# Charger.net
KiCad netlist of a schematic drawn in Altium Designer
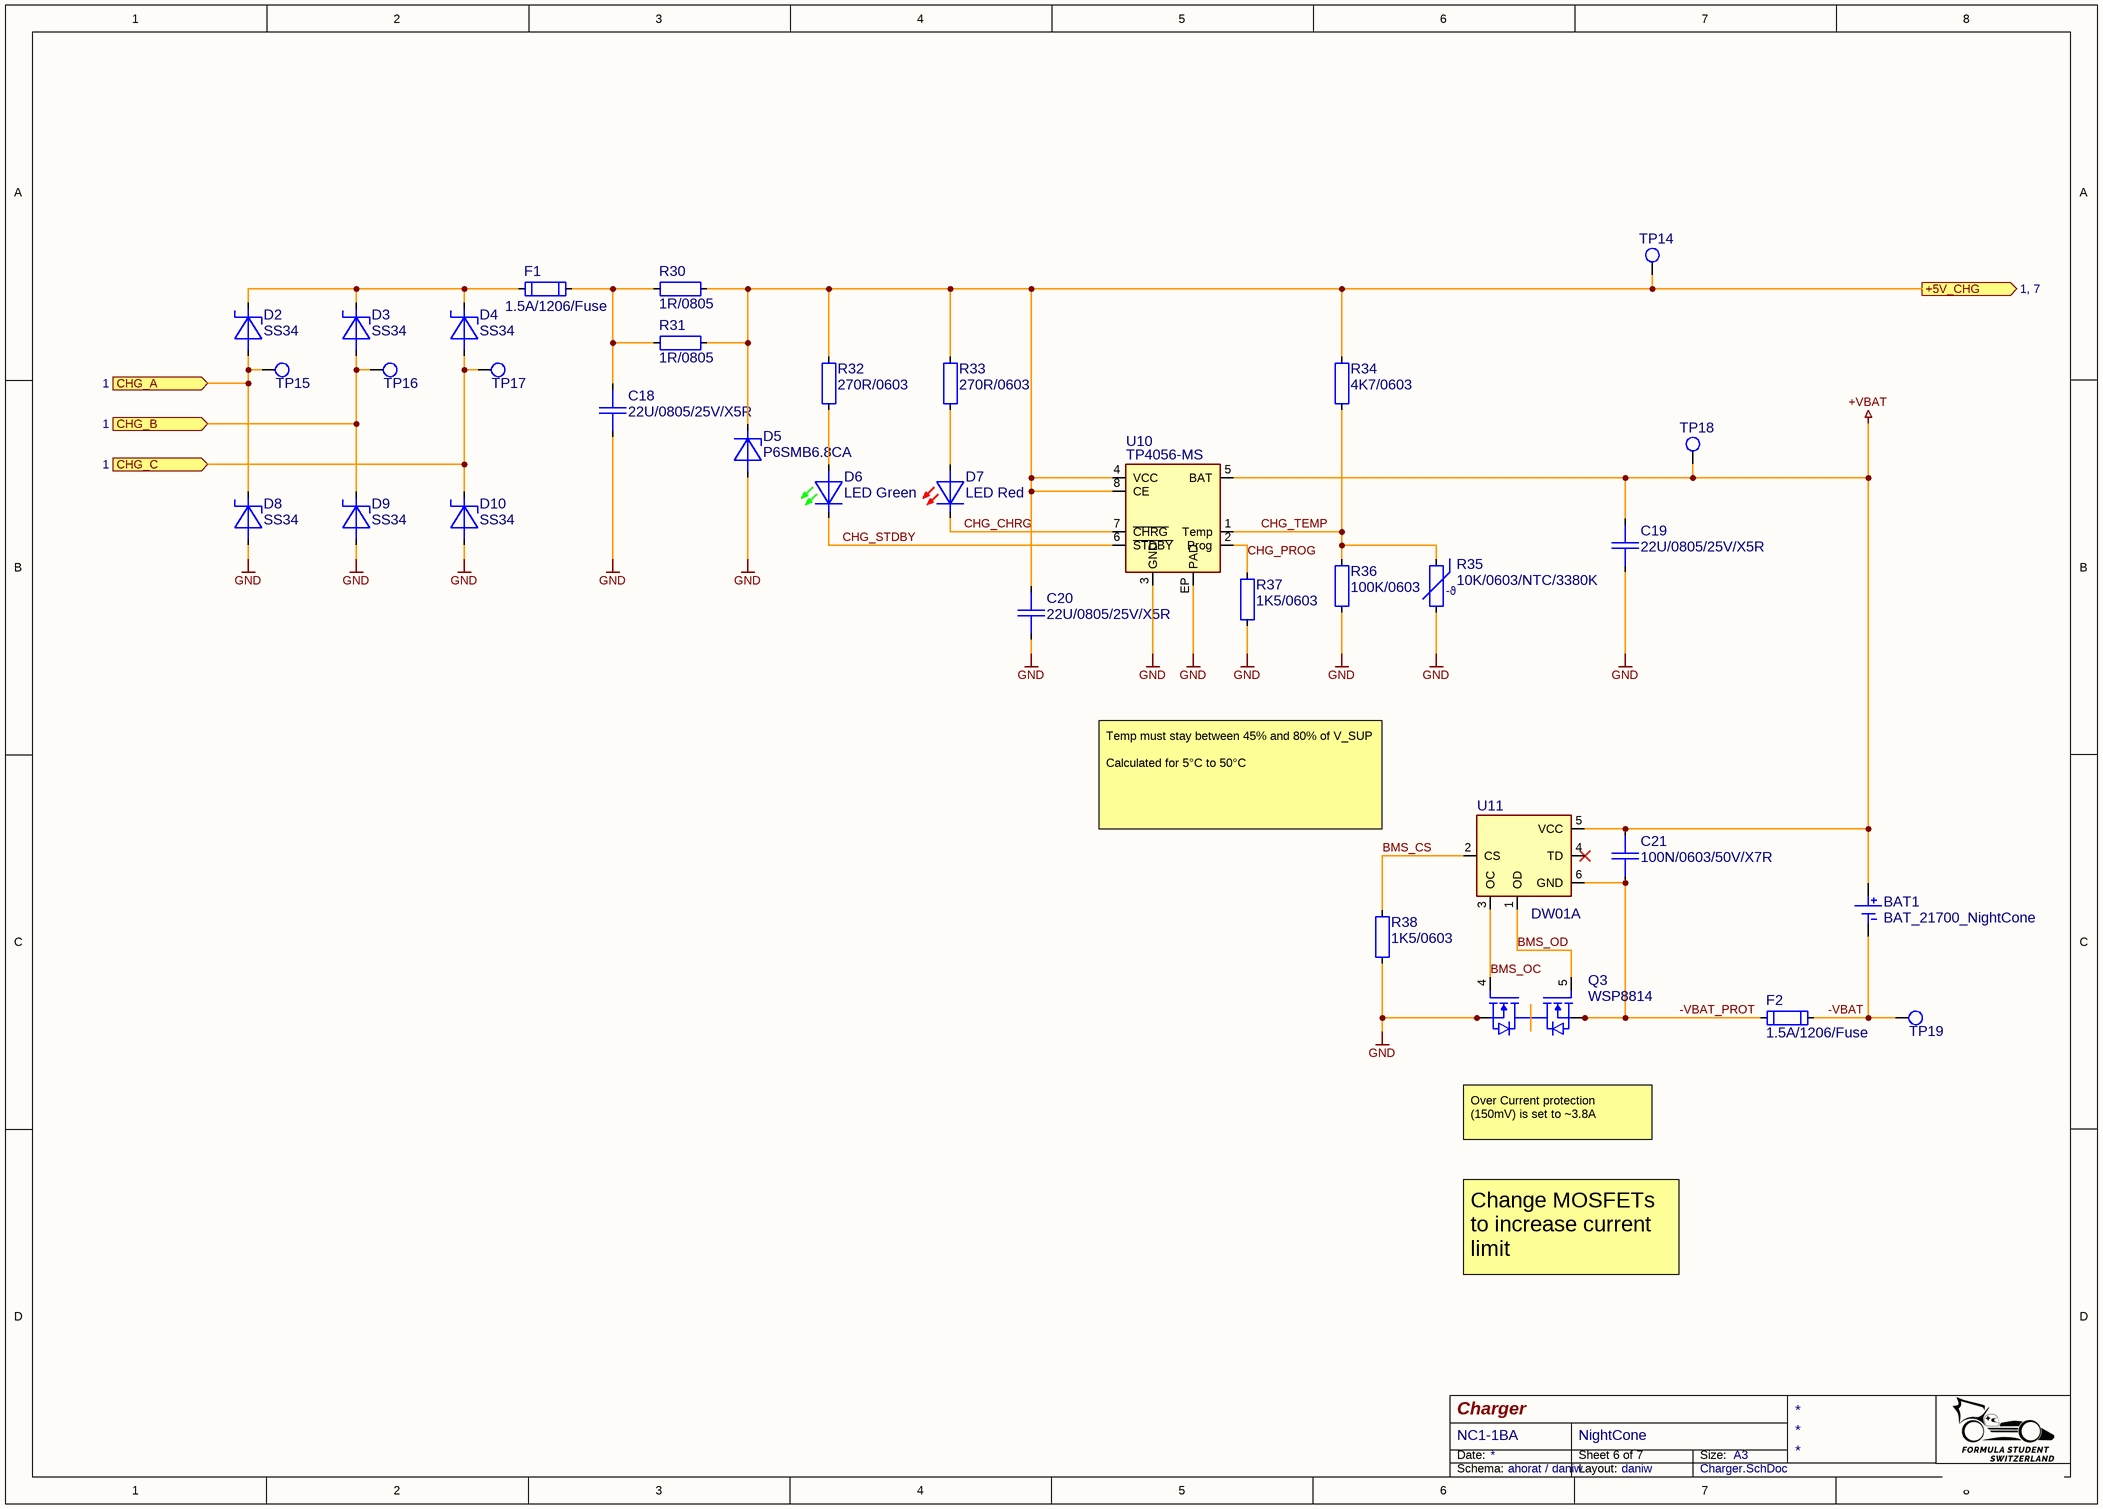
[diagram p0: Charger.SchDoc]

(export (version "E")
  (design (tool "Eeschema 10.0.6"))
  (components
    (comp (ref "BAT1")
      (value "BAT_21700_NightCone")
      (footprint "BAT-21700-NC")
      (description "21700 Battery cell for FSCH nightcone project")
      (fields (field (name "MANUFACTURER") "NONE"))
      (libsource (lib "daniw_altium_lib") (part "Battery_1"))
    )
    (comp (ref "C18")
      (value "22U/0805/25V/X5R")
      (footprint "CAP0805_X7R")
      (description "CAP SM 0805 22uF 25V X5R")
      (fields (field (name "MANUFACTURER") "GENERIC"))
      (libsource (lib "daniw_altium_lib") (part "C"))
    )
    (comp (ref "C19")
      (value "22U/0805/25V/X5R")
      (footprint "CAP0805_X7R")
      (description "CAP SM 0805 22uF 25V X5R")
      (fields (field (name "MANUFACTURER") "GENERIC"))
      (libsource (lib "daniw_altium_lib") (part "C"))
    )
    (comp (ref "C20")
      (value "22U/0805/25V/X5R")
      (footprint "CAP0805_X7R")
      (description "CAP SM 0805 22uF 25V X5R")
      (fields (field (name "MANUFACTURER") "GENERIC"))
      (libsource (lib "daniw_altium_lib") (part "C"))
    )
    (comp (ref "C21")
      (value "100N/0603/50V/X7R")
      (footprint "CAP0603_X7R")
      (description "CAP SM 0603 100nF 50V X7R")
      (fields (field (name "MANUFACTURER") "GENERIC"))
      (libsource (lib "daniw_altium_lib") (part "C"))
    )
    (comp (ref "D2")
      (value "SS34")
      (footprint "DIOM5226X230")
      (description "Si Shottky Diode 3A DO-214AC")
      (fields (field (name "MANUFACTURER") "GENERIC"))
      (libsource (lib "daniw_altium_lib") (part "D_Schottky"))
    )
    (comp (ref "D3")
      (value "SS34")
      (footprint "DIOM5226X230")
      (description "Si Shottky Diode 3A DO-214AC")
      (fields (field (name "MANUFACTURER") "GENERIC"))
      (libsource (lib "daniw_altium_lib") (part "D_Schottky"))
    )
    (comp (ref "D4")
      (value "SS34")
      (footprint "DIOM5226X230")
      (description "Si Shottky Diode 3A DO-214AC")
      (fields (field (name "MANUFACTURER") "GENERIC"))
      (libsource (lib "daniw_altium_lib") (part "D_Schottky"))
    )
    (comp (ref "D5")
      (value "P6SMB6.8CA")
      (footprint "DIOM5436X265")
      (description "10.5V 6.45V 5.8V SMB(DO-214AA) TVS")
      (fields (field (name "MANUFACTURER") "Littelfuse Inc."))
      (libsource (lib "daniw_altium_lib") (part "D_Zener"))
    )
    (comp (ref "D6")
      (value "LED Green")
      (footprint "LED0805_GREEN")
      (description "Generic LED Green 0805")
      (fields (field (name "PART NUMBER") "LED Green 0805") (field (name "MANUFACTURER") "GENERIC"))
      (libsource (lib "daniw_altium_lib") (part "LED_GREEN"))
    )
    (comp (ref "D7")
      (value "LED Red")
      (footprint "LED0805_RED")
      (description "Generic LED Red 0805")
      (fields (field (name "PART NUMBER") "LED Red 0805") (field (name "MANUFACTURER") "GENERIC"))
      (libsource (lib "daniw_altium_lib") (part "LED_RED"))
    )
    (comp (ref "D8")
      (value "SS34")
      (footprint "DIOM5226X230")
      (description "Si Shottky Diode 3A DO-214AC")
      (fields (field (name "MANUFACTURER") "GENERIC"))
      (libsource (lib "daniw_altium_lib") (part "D_Schottky"))
    )
    (comp (ref "D9")
      (value "SS34")
      (footprint "DIOM5226X230")
      (description "Si Shottky Diode 3A DO-214AC")
      (fields (field (name "MANUFACTURER") "GENERIC"))
      (libsource (lib "daniw_altium_lib") (part "D_Schottky"))
    )
    (comp (ref "D10")
      (value "SS34")
      (footprint "DIOM5226X230")
      (description "Si Shottky Diode 3A DO-214AC")
      (fields (field (name "MANUFACTURER") "GENERIC"))
      (libsource (lib "daniw_altium_lib") (part "D_Schottky"))
    )
    (comp (ref "F1")
      (value "1.5A/1206/Fuse")
      (footprint "Fuse1206-0.55-WW")
      (description "Multifuse 1206 1.5A")
      (fields (field (name "MANUFACTURER") "GENERIC"))
      (libsource (lib "daniw_altium_lib") (part "Fuse"))
    )
    (comp (ref "F2")
      (value "1.5A/1206/Fuse")
      (footprint "Fuse1206-0.55-WW")
      (description "Multifuse 1206 1.5A")
      (fields (field (name "MANUFACTURER") "GENERIC"))
      (libsource (lib "daniw_altium_lib") (part "Fuse"))
    )
    (comp (ref "Q3")
      (value "WSP8814")
      (footprint "SOP065P650X110-8-NW")
      (description "20V 9A 7.6mΩ@4.5V,9A 1.25W 1.2V@250uA 2 N-Channel TSSOP-8")
      (fields (field (name "MANUFACTURER") "Winsok Semicon"))
      (libsource (lib "daniw_altium_lib") (part "WSP8814"))
    )
    (comp (ref "R30")
      (value "1R/0805")
      (footprint "R0805-0.50-WW")
      (description "RES SM 0805 1R")
      (fields (field (name "MANUFACTURER") "GENERIC"))
      (libsource (lib "daniw_altium_lib") (part "R"))
    )
    (comp (ref "R31")
      (value "1R/0805")
      (footprint "R0805-0.50-WW")
      (description "RES SM 0805 1R")
      (fields (field (name "MANUFACTURER") "GENERIC"))
      (libsource (lib "daniw_altium_lib") (part "R"))
    )
    (comp (ref "R32")
      (value "270R/0603")
      (footprint "R0603-0.40-WW")
      (description "RES SM 0603 270R")
      (fields (field (name "MANUFACTURER") "GENERIC"))
      (libsource (lib "daniw_altium_lib") (part "R"))
    )
    (comp (ref "R33")
      (value "270R/0603")
      (footprint "R0603-0.40-WW")
      (description "RES SM 0603 270R")
      (fields (field (name "MANUFACTURER") "GENERIC"))
      (libsource (lib "daniw_altium_lib") (part "R"))
    )
    (comp (ref "R34")
      (value "4K7/0603")
      (footprint "R0603-0.40-WW")
      (description "RES SM 0603 4K7")
      (fields (field (name "MANUFACTURER") "GENERIC"))
      (libsource (lib "daniw_altium_lib") (part "R"))
    )
    (comp (ref "R35")
      (value "10K/0603/NTC/3380K")
      (footprint "R0603-0.40-WW")
      (description "RES NTC SM 0603 10K")
      (fields (field (name "MANUFACTURER") "GENERIC"))
      (libsource (lib "daniw_altium_lib") (part "R_NTC"))
    )
    (comp (ref "R36")
      (value "100K/0603")
      (footprint "R0603-0.40-WW")
      (description "RES SM 0603 100K")
      (fields (field (name "MANUFACTURER") "GENERIC"))
      (libsource (lib "daniw_altium_lib") (part "R"))
    )
    (comp (ref "R37")
      (value "1K5/0603")
      (footprint "R0603-0.40-WW")
      (description "RES SM 0603 1K5")
      (fields (field (name "MANUFACTURER") "GENERIC"))
      (libsource (lib "daniw_altium_lib") (part "R"))
    )
    (comp (ref "R38")
      (value "1K5/0603")
      (footprint "R0603-0.40-WW")
      (description "RES SM 0603 1K5")
      (fields (field (name "MANUFACTURER") "GENERIC"))
      (libsource (lib "daniw_altium_lib") (part "R"))
    )
    (comp (ref "TP14")
      (value "TP_THD_1.5/0.8")
      (footprint "TP_THD_1.5/0.8")
      (description "THT Test Point 1.5/0.8mm")
      (fields (field (name "MANUFACTURER") "NONE"))
      (libsource (lib "daniw_altium_lib") (part "Testpoint"))
    )
    (comp (ref "TP15")
      (value "TP_THD_1.5/0.8")
      (footprint "TP_THD_1.5/0.8")
      (description "THT Test Point 1.5/0.8mm")
      (fields (field (name "MANUFACTURER") "NONE"))
      (libsource (lib "daniw_altium_lib") (part "Testpoint"))
    )
    (comp (ref "TP16")
      (value "TP_THD_1.5/0.8")
      (footprint "TP_THD_1.5/0.8")
      (description "THT Test Point 1.5/0.8mm")
      (fields (field (name "MANUFACTURER") "NONE"))
      (libsource (lib "daniw_altium_lib") (part "Testpoint"))
    )
    (comp (ref "TP17")
      (value "TP_THD_1.5/0.8")
      (footprint "TP_THD_1.5/0.8")
      (description "THT Test Point 1.5/0.8mm")
      (fields (field (name "MANUFACTURER") "NONE"))
      (libsource (lib "daniw_altium_lib") (part "Testpoint"))
    )
    (comp (ref "TP18")
      (value "TP_THD_1.5/0.8")
      (footprint "TP_THD_1.5/0.8")
      (description "THT Test Point 1.5/0.8mm")
      (fields (field (name "MANUFACTURER") "NONE"))
      (libsource (lib "daniw_altium_lib") (part "Testpoint"))
    )
    (comp (ref "TP19")
      (value "TP_THD_1.5/0.8")
      (footprint "TP_THD_1.5/0.8")
      (description "THT Test Point 1.5/0.8mm")
      (fields (field (name "MANUFACTURER") "NONE"))
      (libsource (lib "daniw_altium_lib") (part "Testpoint"))
    )
    (comp (ref "U10")
      (value "TP4056-MS")
      (footprint "SOP127P600X155-9-TH330x240-NW")
      (description "1A Standalone Linear Li-lon Battery Charger with Thermal Regulation in SOP-8")
      (fields (field (name "MANUFACTURER") "MSKSEMI"))
      (libsource (lib "daniw_altium_lib") (part "TP4056"))
    )
    (comp (ref "U11")
      (value "DW01A")
      (footprint "SOT2395P280X125-6-SW")
      (description "Single Cell Lithium-ion battery protection IC")
      (fields (field (name "MANUFACTURER") "PUOLOP"))
      (libsource (lib "daniw_altium_lib") (part "DW01A"))
    )
  )
  (nets
    (net (code "1") (name "+VBAT") (class "Default")
      (node (ref "BAT1") (pin "1") (pinfunction "+_1") (pintype "passive"))
      (node (ref "C19") (pin "1") (pinfunction "1_1") (pintype "passive"))
      (node (ref "C21") (pin "1") (pinfunction "1_1") (pintype "passive"))
      (node (ref "TP18") (pin "1") (pinfunction "1_1") (pintype "passive"))
      (node (ref "U10") (pin "5") (pinfunction "BAT_5") (pintype "passive"))
      (node (ref "U11") (pin "5") (pinfunction "VCC_5") (pintype "passive"))
    )
    (net (code "2") (name "/+5V_CHG") (class "Default")
      (node (ref "C20") (pin "1") (pinfunction "1_1") (pintype "passive"))
      (node (ref "D5") (pin "1") (pinfunction "1_1") (pintype "passive"))
      (node (ref "R30") (pin "2") (pinfunction "2_2") (pintype "passive"))
      (node (ref "R31") (pin "2") (pinfunction "2_2") (pintype "passive"))
      (node (ref "R32") (pin "1") (pinfunction "1_1") (pintype "passive"))
      (node (ref "R33") (pin "1") (pinfunction "1_1") (pintype "passive"))
      (node (ref "R34") (pin "1") (pinfunction "1_1") (pintype "passive"))
      (node (ref "TP14") (pin "1") (pinfunction "1_1") (pintype "passive"))
      (node (ref "U10") (pin "4") (pinfunction "VCC_4") (pintype "passive"))
      (node (ref "U10") (pin "8") (pinfunction "CE_8") (pintype "passive"))
    )
    (net (code "3") (name "/-VBAT") (class "Default")
      (node (ref "BAT1") (pin "2") (pinfunction "-_2") (pintype "passive"))
      (node (ref "F2") (pin "1") (pinfunction "1_1") (pintype "passive"))
      (node (ref "TP19") (pin "1") (pinfunction "1_1") (pintype "passive"))
    )
    (net (code "4") (name "/-VBAT_PROT") (class "Default")
      (node (ref "C21") (pin "2") (pinfunction "2_2") (pintype "passive"))
      (node (ref "F2") (pin "2") (pinfunction "2_2") (pintype "passive"))
      (node (ref "Q3") (pin "6") (pinfunction "S2_6") (pintype "passive"))
      (node (ref "Q3") (pin "7") (pinfunction "S2_7") (pintype "passive"))
      (node (ref "U11") (pin "6") (pinfunction "GND_6") (pintype "passive"))
    )
    (net (code "5") (name "/BMS_CS") (class "Default")
      (node (ref "R38") (pin "1") (pinfunction "1_1") (pintype "passive"))
      (node (ref "U11") (pin "2") (pinfunction "CS_2") (pintype "passive"))
    )
    (net (code "6") (name "/BMS_OC") (class "Default")
      (node (ref "Q3") (pin "4") (pinfunction "G1_4") (pintype "passive"))
      (node (ref "U11") (pin "3") (pinfunction "OC_3") (pintype "passive"))
    )
    (net (code "7") (name "/BMS_OD") (class "Default")
      (node (ref "Q3") (pin "5") (pinfunction "G2_5") (pintype "passive"))
      (node (ref "U11") (pin "1") (pinfunction "OD_1") (pintype "passive"))
    )
    (net (code "8") (name "/CHG_A") (class "Default")
      (node (ref "D2") (pin "2") (pinfunction "2_2") (pintype "passive"))
      (node (ref "D8") (pin "1") (pinfunction "1_1") (pintype "passive"))
      (node (ref "TP15") (pin "1") (pinfunction "1_1") (pintype "passive"))
    )
    (net (code "9") (name "/CHG_B") (class "Default")
      (node (ref "D3") (pin "2") (pinfunction "2_2") (pintype "passive"))
      (node (ref "D9") (pin "1") (pinfunction "1_1") (pintype "passive"))
      (node (ref "TP16") (pin "1") (pinfunction "1_1") (pintype "passive"))
    )
    (net (code "10") (name "/CHG_C") (class "Default")
      (node (ref "D10") (pin "1") (pinfunction "1_1") (pintype "passive"))
      (node (ref "D4") (pin "2") (pinfunction "2_2") (pintype "passive"))
      (node (ref "TP17") (pin "1") (pinfunction "1_1") (pintype "passive"))
    )
    (net (code "11") (name "/CHG_CHRG") (class "Default")
      (node (ref "D7") (pin "1") (pinfunction "1_1") (pintype "passive"))
      (node (ref "U10") (pin "7") (pinfunction "~{CHRG}_7") (pintype "passive"))
    )
    (net (code "12") (name "/CHG_PROG") (class "Default")
      (node (ref "R37") (pin "1") (pinfunction "1_1") (pintype "passive"))
      (node (ref "U10") (pin "2") (pinfunction "Prog_2") (pintype "passive"))
    )
    (net (code "13") (name "/CHG_STDBY") (class "Default")
      (node (ref "D6") (pin "1") (pinfunction "1_1") (pintype "passive"))
      (node (ref "U10") (pin "6") (pinfunction "~{STDBY}_6") (pintype "passive"))
    )
    (net (code "14") (name "/CHG_TEMP") (class "Default")
      (node (ref "R34") (pin "2") (pinfunction "2_2") (pintype "passive"))
      (node (ref "R35") (pin "1") (pinfunction "1_1") (pintype "passive"))
      (node (ref "R36") (pin "1") (pinfunction "1_1") (pintype "passive"))
      (node (ref "U10") (pin "1") (pinfunction "Temp_1") (pintype "passive"))
    )
    (net (code "15") (name "GND") (class "Default")
      (node (ref "C18") (pin "2") (pinfunction "2_2") (pintype "passive"))
      (node (ref "C19") (pin "2") (pinfunction "2_2") (pintype "passive"))
      (node (ref "C20") (pin "2") (pinfunction "2_2") (pintype "passive"))
      (node (ref "D10") (pin "2") (pinfunction "2_2") (pintype "passive"))
      (node (ref "D5") (pin "2") (pinfunction "2_2") (pintype "passive"))
      (node (ref "D8") (pin "2") (pinfunction "2_2") (pintype "passive"))
      (node (ref "D9") (pin "2") (pinfunction "2_2") (pintype "passive"))
      (node (ref "Q3") (pin "2") (pinfunction "S1_2") (pintype "passive"))
      (node (ref "Q3") (pin "3") (pinfunction "S1_3") (pintype "passive"))
      (node (ref "R35") (pin "2") (pinfunction "2_2") (pintype "passive"))
      (node (ref "R36") (pin "2") (pinfunction "2_2") (pintype "passive"))
      (node (ref "R37") (pin "2") (pinfunction "2_2") (pintype "passive"))
      (node (ref "R38") (pin "2") (pinfunction "2_2") (pintype "passive"))
      (node (ref "U10") (pin "3") (pinfunction "GND_3") (pintype "passive"))
      (node (ref "U10") (pin "EP") (pinfunction "PAD_EP") (pintype "passive"))
    )
    (net (code "16") (name "Net-(C18-Pad1)") (class "Default")
      (node (ref "C18") (pin "1") (pinfunction "1_1") (pintype "passive"))
      (node (ref "F1") (pin "2") (pinfunction "2_2") (pintype "passive"))
      (node (ref "R30") (pin "1") (pinfunction "1_1") (pintype "passive"))
      (node (ref "R31") (pin "1") (pinfunction "1_1") (pintype "passive"))
    )
    (net (code "17") (name "Net-(D2-Pad1)") (class "Default")
      (node (ref "D2") (pin "1") (pinfunction "1_1") (pintype "passive"))
      (node (ref "D3") (pin "1") (pinfunction "1_1") (pintype "passive"))
      (node (ref "D4") (pin "1") (pinfunction "1_1") (pintype "passive"))
      (node (ref "F1") (pin "1") (pinfunction "1_1") (pintype "passive"))
    )
    (net (code "18") (name "Net-(D6-Pad2)") (class "Default")
      (node (ref "D6") (pin "2") (pinfunction "2_2") (pintype "passive"))
      (node (ref "R32") (pin "2") (pinfunction "2_2") (pintype "passive"))
    )
    (net (code "19") (name "Net-(D7-Pad2)") (class "Default")
      (node (ref "D7") (pin "2") (pinfunction "2_2") (pintype "passive"))
      (node (ref "R33") (pin "2") (pinfunction "2_2") (pintype "passive"))
    )
    (net (code "20") (name "Net-(Q3-D-Pad1)") (class "Default")
      (node (ref "Q3") (pin "1") (pinfunction "D_1") (pintype "passive"))
      (node (ref "Q3") (pin "8") (pinfunction "D_8") (pintype "passive"))
    )
    (net (code "21") (name "unconnected-(U11-TD-Pad4)") (class "Default")
      (node (ref "U11") (pin "4") (pinfunction "TD_4") (pintype "passive+no_connect"))
    )
  )
)
